# SAME51_PINOUT.net
KiCad netlist of a schematic drawn in Altium Designer
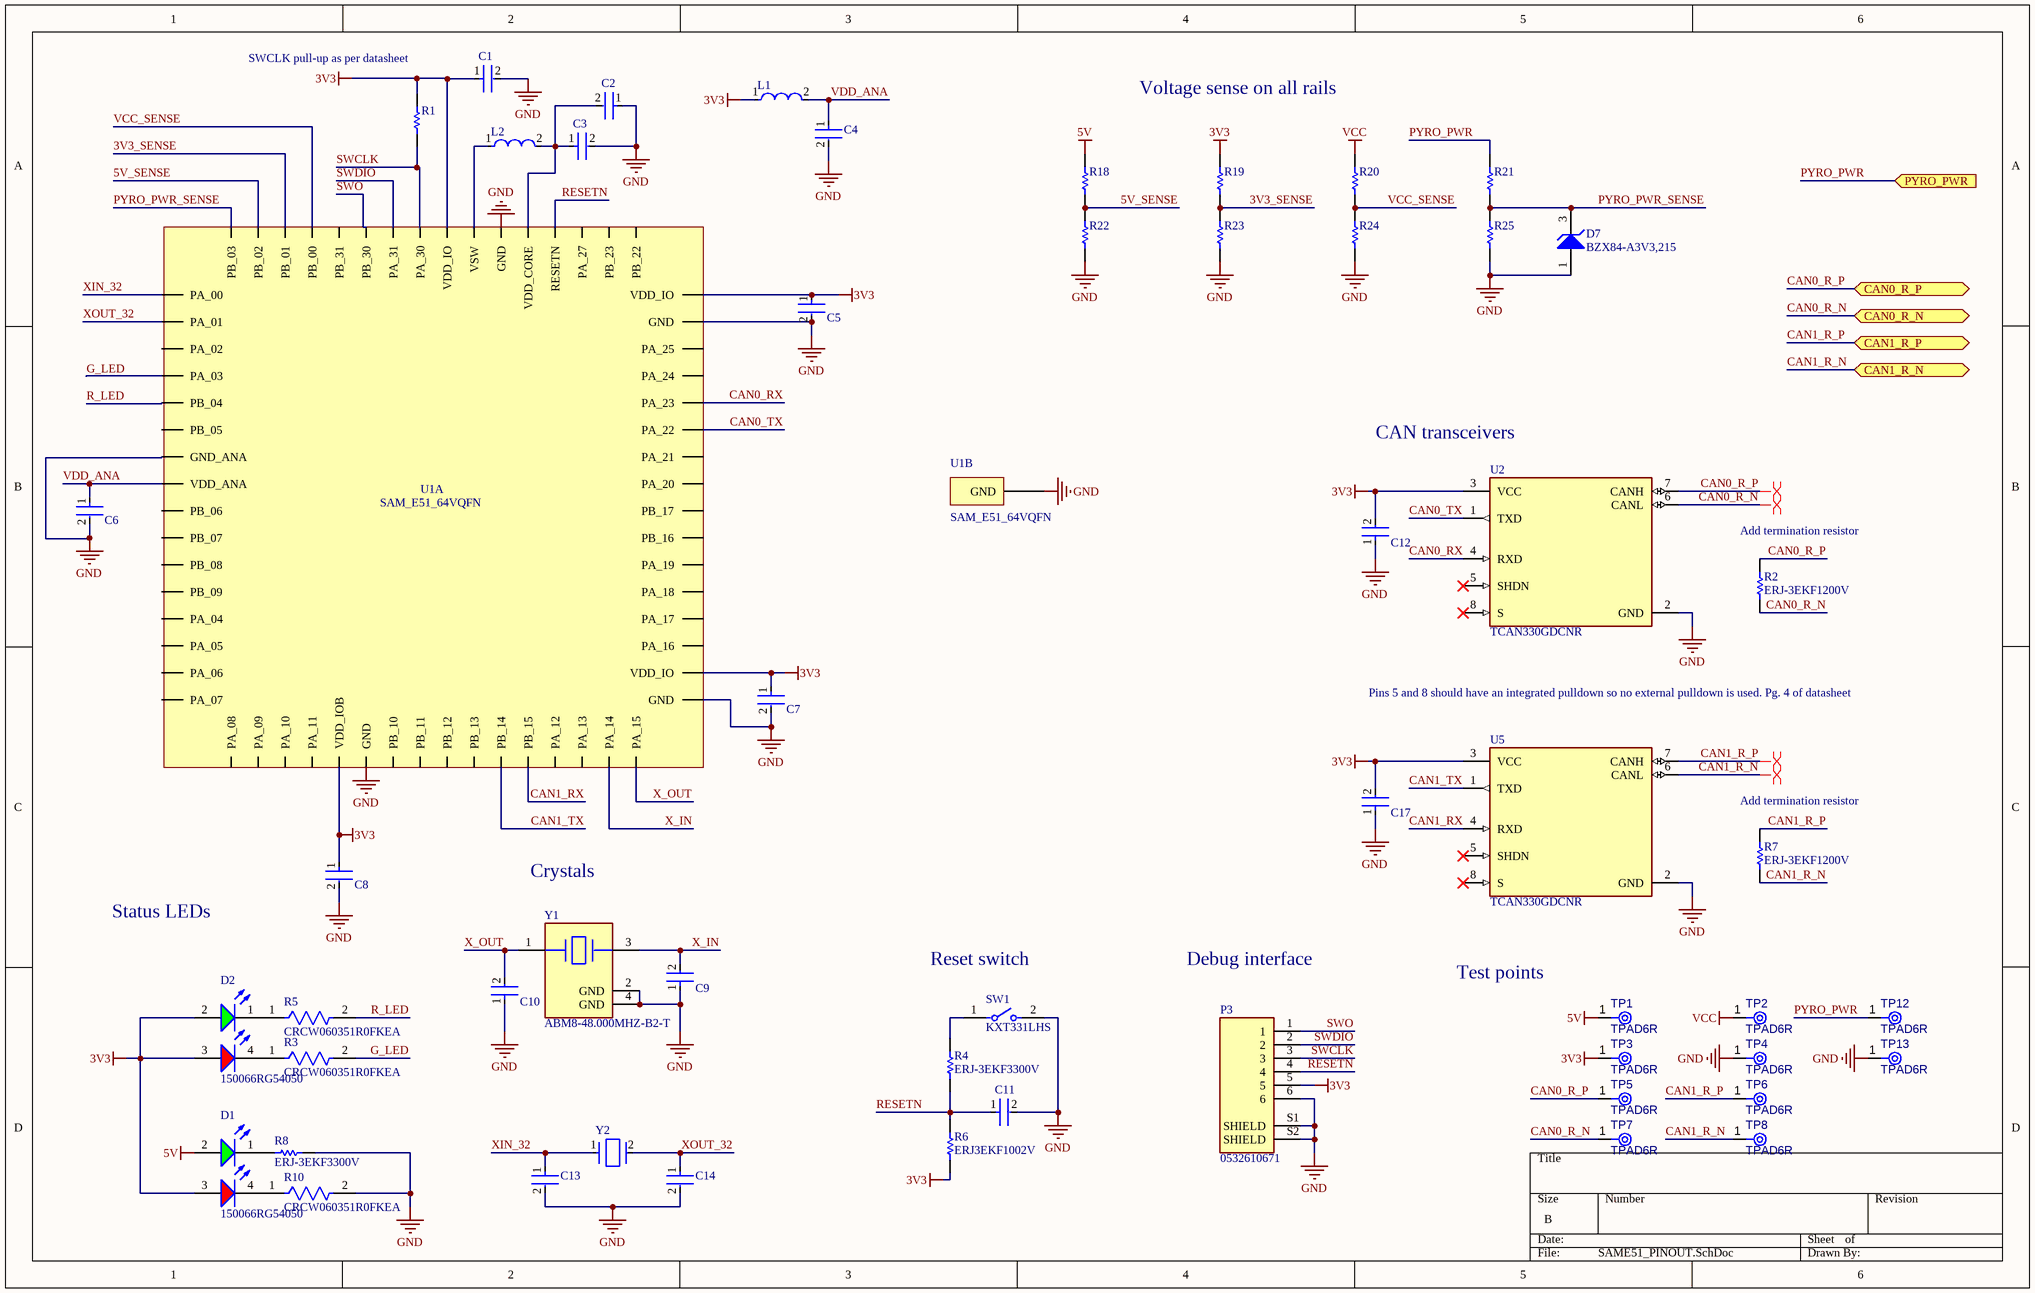
[diagram p0: SAME51_PINOUT.SchDoc]

(export (version "E")
  (design (tool "Eeschema 10.0.6"))
  (components
    (comp (ref "C1")
      (value "C0402C104K8PACTU")
      (footprint "FP-C0402-BB-MFG")
      (description "CAP CER 0.1UF 10V X5R 0402")
      (fields (field (name "MANUFACTURER") "Kemet") (field (name "TOLERANCE") "0.1"))
      (libsource (lib "Altium Content Vault") (part "b4654b650e69147ec39a6b967a45e02"))
    )
    (comp (ref "C2")
      (value "GRM155R60J475ME47D")
      (footprint "FP-GRM155-0_1-IPC_B")
      (description "Chip Multilayer Ceramic Capacitors for General Purpose, 0402, 4.7uF, X5R, 15%, 20%, 6.3V")
      (fields (field (name "VOLTAGE") "6.3V") (field (name "TOLERANCE") "20%"))
      (libsource (lib "Altium Content Vault") (part "11868f565c42a9108669ba33697ecf6"))
    )
    (comp (ref "C3")
      (value "C0402C104K8PACTU")
      (footprint "FP-C0402-BB-MFG")
      (description "CAP CER 0.1UF 10V X5R 0402")
      (fields (field (name "MANUFACTURER") "Kemet") (field (name "TOLERANCE") "0.1"))
      (libsource (lib "Altium Content Vault") (part "b4654b650e69147ec39a6b967a45e02"))
    )
    (comp (ref "C4")
      (value "C0805C106K8PACTU")
      (footprint "FP-C0805C-DG-MFG")
      (description "CAP CER 10UF 10V X5R 0805")
      (fields (field (name "TOLERANCE") "10%") (field (name "MANUFACTURER") "Kemet"))
      (libsource (lib "Altium Content Vault") (part "11868f565c42a9108669ba33697ecf6"))
    )
    (comp (ref "C5")
      (value "C0402C104K8PACTU")
      (footprint "FP-C0402-BB-MFG")
      (description "CAP CER 0.1UF 10V X5R 0402")
      (fields (field (name "MANUFACTURER") "Kemet") (field (name "TOLERANCE") "0.1"))
      (libsource (lib "Altium Content Vault") (part "b4654b650e69147ec39a6b967a45e02"))
    )
    (comp (ref "C6")
      (value "C0402C104K8PACTU")
      (footprint "FP-C0402-BB-MFG")
      (description "CAP CER 0.1UF 10V X5R 0402")
      (fields (field (name "MANUFACTURER") "Kemet") (field (name "TOLERANCE") "0.1"))
      (libsource (lib "Altium Content Vault") (part "b4654b650e69147ec39a6b967a45e02"))
    )
    (comp (ref "C7")
      (value "C0402C104K8PACTU")
      (footprint "FP-C0402-BB-MFG")
      (description "CAP CER 0.1UF 10V X5R 0402")
      (fields (field (name "MANUFACTURER") "Kemet") (field (name "TOLERANCE") "0.1"))
      (libsource (lib "Altium Content Vault") (part "b4654b650e69147ec39a6b967a45e02"))
    )
    (comp (ref "C8")
      (value "C0402C104K8PACTU")
      (footprint "FP-C0402-BB-MFG")
      (description "CAP CER 0.1UF 10V X5R 0402")
      (fields (field (name "MANUFACTURER") "Kemet") (field (name "TOLERANCE") "0.1"))
      (libsource (lib "Altium Content Vault") (part "b4654b650e69147ec39a6b967a45e02"))
    )
    (comp (ref "C9")
      (value "08051A6R8CAT2A")
      (footprint "FP-0805-L_2_01_0_2-W_1_25-MFG")
      (description "General Purpose Ceramic Capacitor, 0805, 6.8pF, 0.25pF, C0G, 30ppm/°C, 100V")
      (fields (field (name "VOLTAGE") "100V") (field (name "TOLERANCE") "5%"))
      (libsource (lib "Altium Content Vault") (part "02cd4be3c70576c341d710602a673aa"))
    )
    (comp (ref "C10")
      (value "08051A6R8CAT2A")
      (footprint "FP-0805-L_2_01_0_2-W_1_25-MFG")
      (description "General Purpose Ceramic Capacitor, 0805, 6.8pF, 0.25pF, C0G, 30ppm/°C, 100V")
      (fields (field (name "VOLTAGE") "100V") (field (name "TOLERANCE") "5%"))
      (libsource (lib "Altium Content Vault") (part "02cd4be3c70576c341d710602a673aa"))
    )
    (comp (ref "C11")
      (value "C0402C104K8PACTU")
      (footprint "FP-C0402-BB-MFG")
      (description "CAP CER 0.1UF 10V X5R 0402")
      (fields (field (name "MANUFACTURER") "Kemet") (field (name "TOLERANCE") "0.1"))
      (libsource (lib "Altium Content Vault") (part "b4654b650e69147ec39a6b967a45e02"))
    )
    (comp (ref "C12")
      (value "C0402C104K8PACTU")
      (footprint "FP-C0402-BB-MFG")
      (description "CAP CER 0.1UF 10V X5R 0402")
      (fields (field (name "MANUFACTURER") "Kemet") (field (name "TOLERANCE") "0.1"))
      (libsource (lib "Altium Content Vault") (part "b4654b650e69147ec39a6b967a45e02"))
    )
    (comp (ref "C13")
      (value "C0805C180J5GACTU")
      (footprint "FP-C0805C-DN-MFG")
      (description "CAP CER 18PF 50V C0G/NP0 0805")
      (fields
        (field (name "OCTOPART") "https://octopart.com/c0805c180j5gactu-kemet-144810")
        (field (name "TOLERANCE") "0.05")
      )
      (libsource (lib "Altium Content Vault") (part "b4654b650e69147ec39a6b967a45e02"))
    )
    (comp (ref "C14")
      (value "C0805C180J5GACTU")
      (footprint "FP-C0805C-DN-MFG")
      (description "CAP CER 18PF 50V C0G/NP0 0805")
      (fields
        (field (name "OCTOPART") "https://octopart.com/c0805c180j5gactu-kemet-144810")
        (field (name "TOLERANCE") "0.05")
      )
      (libsource (lib "Altium Content Vault") (part "b4654b650e69147ec39a6b967a45e02"))
    )
    (comp (ref "C17")
      (value "C0402C104K8PACTU")
      (footprint "FP-C0402-BB-MFG")
      (description "CAP CER 0.1UF 10V X5R 0402")
      (fields (field (name "MANUFACTURER") "Kemet") (field (name "TOLERANCE") "0.1"))
      (libsource (lib "Altium Content Vault") (part "b4654b650e69147ec39a6b967a45e02"))
    )
    (comp (ref "D1")
      (value "150066RG54050")
      (footprint "WL-SBCD_0606")
      (description "Led, Red/Grn, 180Mcd/230Mcd, 624Nm/525Nm Rohs Compliant: Yes")
      (libsource (lib "uORocketry Hardware") (part "WL-SBCD_0606_Red & Green"))
    )
    (comp (ref "D2")
      (value "150066RG54050")
      (footprint "WL-SBCD_0606")
      (description "Led, Red/Grn, 180Mcd/230Mcd, 624Nm/525Nm Rohs Compliant: Yes")
      (libsource (lib "uORocketry Hardware") (part "WL-SBCD_0606_Red & Green"))
    )
    (comp (ref "D7")
      (value "BZX84-A3V3,215")
      (footprint "SOT95P230X110-3N")
      (description "DIODE ZENER 3.3V 250MW SOT23")
      (libsource (lib "uORocketry Hardware") (part "BZX84-A3V3,215"))
    )
    (comp (ref "L1")
      (value "NR6028T100M")
      (footprint "FP-NR6028-MFG")
      (description "SMD Power Inductors 10uH ±20% 1.9A 84.5mΩ")
      (fields (field (name "TOLERANCE") "20%"))
      (libsource (lib "Altium Content Vault") (part "725321dda6339637d4d059423bc1c3c"))
    )
    (comp (ref "L2")
      (value "NR6028T100M")
      (footprint "FP-NR6028-MFG")
      (description "SMD Power Inductors 10uH ±20% 1.9A 84.5mΩ")
      (fields (field (name "TOLERANCE") "20%"))
      (libsource (lib "Altium Content Vault") (part "725321dda6339637d4d059423bc1c3c"))
    )
    (comp (ref "P3")
      (value "0532610671")
      (footprint "0532610671-Footprint-1")
      (description "Conn Shrouded Header (4 Sides) HDR 6 POS 1.25mm Solder RA Side Entry SMD PicoBlade™ T/R")
      (libsource (lib "uORocketry Hardware") (part "0532610671"))
    )
    (comp (ref "R1")
      (value "ERJ3EKF1002V")
      (footprint "RESC1609X55X30LL15T15")
      (description "Chip Resistor, 10 KOhm, +/- 1%, 0.1 W, -55 to 155 degC, 0603 (1608 Metric), RoHS, Tape and Reel")
      (fields (field (name "TOLERANCE") "1%") (field (name "MANUFACTURER") "Panasonic"))
      (libsource (lib "Altium Content Vault") (part "RES-2"))
    )
    (comp (ref "R2")
      (value "ERJ-3EKF1200V")
      (footprint "RESC1609X55X30ML15T15")
      (description "Chip Resistor, 120 Ohm, +/- 1%, 0.1 W, -55 to 155 degC, 0603 (1608 Metric), RoHS, Tape and Reel")
      (fields (field (name "TOLERANCE") "1%") (field (name "MANUFACTURER") "Panasonic"))
      (libsource (lib "Altium Content Vault") (part "RES-2"))
    )
    (comp (ref "R3")
      (value "CRCW060351R0FKEA")
      (footprint "FP-CRCW0603-e3-MFG")
      (description "RES Thick Film, 51Ω, 1%, 0.1W, 100ppm/°C, 0603")
      (fields (field (name "TOLERANCE") "1%"))
      (libsource (lib "Altium Content Vault") (part "1029c3af85768c4190bb7ad29bc67b5"))
    )
    (comp (ref "R4")
      (value "ERJ-3EKF3300V")
      (footprint "RESC1608X55X30LL15T15")
      (description "Chip Resistor, 330 Ohm, +/- 1%, 0.1 W, -55 to 155 degC, 0603 (1608 Metric), RoHS, Tape and Reel")
      (libsource (lib "Altium Content Vault") (part "RES-2"))
    )
    (comp (ref "R5")
      (value "CRCW060351R0FKEA")
      (footprint "FP-CRCW0603-e3-MFG")
      (description "RES Thick Film, 51Ω, 1%, 0.1W, 100ppm/°C, 0603")
      (fields (field (name "TOLERANCE") "1%"))
      (libsource (lib "Altium Content Vault") (part "1029c3af85768c4190bb7ad29bc67b5"))
    )
    (comp (ref "R6")
      (value "ERJ3EKF1002V")
      (footprint "RESC1609X55X30LL15T15")
      (description "Chip Resistor, 10 KOhm, +/- 1%, 0.1 W, -55 to 155 degC, 0603 (1608 Metric), RoHS, Tape and Reel")
      (fields (field (name "TOLERANCE") "1%") (field (name "MANUFACTURER") "Panasonic"))
      (libsource (lib "Altium Content Vault") (part "RES-2"))
    )
    (comp (ref "R7")
      (value "ERJ-3EKF1200V")
      (footprint "RESC1609X55X30ML15T15")
      (description "Chip Resistor, 120 Ohm, +/- 1%, 0.1 W, -55 to 155 degC, 0603 (1608 Metric), RoHS, Tape and Reel")
      (fields (field (name "TOLERANCE") "1%") (field (name "MANUFACTURER") "Panasonic"))
      (libsource (lib "Altium Content Vault") (part "RES-2"))
    )
    (comp (ref "R8")
      (value "ERJ-3EKF3300V")
      (footprint "RESC1608X55X30LL15T15")
      (description "Chip Resistor, 330 Ohm, +/- 1%, 0.1 W, -55 to 155 degC, 0603 (1608 Metric), RoHS, Tape and Reel")
      (libsource (lib "Altium Content Vault") (part "RES-2"))
    )
    (comp (ref "R10")
      (value "CRCW060351R0FKEA")
      (footprint "FP-CRCW0603-e3-MFG")
      (description "RES Thick Film, 51Ω, 1%, 0.1W, 100ppm/°C, 0603")
      (fields (field (name "TOLERANCE") "1%"))
      (libsource (lib "Altium Content Vault") (part "1029c3af85768c4190bb7ad29bc67b5"))
    )
    (comp (ref "R18")
      (value "ERJ3EKF1002V")
      (footprint "RESC1609X55X30LL15T15")
      (description "Chip Resistor, 10 KOhm, +/- 1%, 0.1 W, -55 to 155 degC, 0603 (1608 Metric), RoHS, Tape and Reel")
      (fields (field (name "TOLERANCE") "1%") (field (name "MANUFACTURER") "Panasonic"))
      (libsource (lib "Altium Content Vault") (part "RES-2"))
    )
    (comp (ref "R19")
      (value "ERJ3EKF1002V")
      (footprint "RESC1609X55X30LL15T15")
      (description "Chip Resistor, 10 KOhm, +/- 1%, 0.1 W, -55 to 155 degC, 0603 (1608 Metric), RoHS, Tape and Reel")
      (fields (field (name "TOLERANCE") "1%") (field (name "MANUFACTURER") "Panasonic"))
      (libsource (lib "Altium Content Vault") (part "RES-2"))
    )
    (comp (ref "R20")
      (value "ERJ3EKF1002V")
      (footprint "RESC1609X55X30LL15T15")
      (description "Chip Resistor, 10 KOhm, +/- 1%, 0.1 W, -55 to 155 degC, 0603 (1608 Metric), RoHS, Tape and Reel")
      (fields (field (name "TOLERANCE") "1%") (field (name "MANUFACTURER") "Panasonic"))
      (libsource (lib "Altium Content Vault") (part "RES-2"))
    )
    (comp (ref "R21")
      (value "ERJ3EKF1002V")
      (footprint "RESC1609X55X30LL15T15")
      (description "Chip Resistor, 10 KOhm, +/- 1%, 0.1 W, -55 to 155 degC, 0603 (1608 Metric), RoHS, Tape and Reel")
      (fields (field (name "TOLERANCE") "1%") (field (name "MANUFACTURER") "Panasonic"))
      (libsource (lib "Altium Content Vault") (part "RES-2"))
    )
    (comp (ref "R22")
      (value "ERJ3EKF1002V")
      (footprint "RESC1609X55X30LL15T15")
      (description "Chip Resistor, 10 KOhm, +/- 1%, 0.1 W, -55 to 155 degC, 0603 (1608 Metric), RoHS, Tape and Reel")
      (fields (field (name "TOLERANCE") "1%") (field (name "MANUFACTURER") "Panasonic"))
      (libsource (lib "Altium Content Vault") (part "RES-2"))
    )
    (comp (ref "R23")
      (value "ERJ3EKF1002V")
      (footprint "RESC1609X55X30LL15T15")
      (description "Chip Resistor, 10 KOhm, +/- 1%, 0.1 W, -55 to 155 degC, 0603 (1608 Metric), RoHS, Tape and Reel")
      (fields (field (name "TOLERANCE") "1%") (field (name "MANUFACTURER") "Panasonic"))
      (libsource (lib "Altium Content Vault") (part "RES-2"))
    )
    (comp (ref "R24")
      (value "CRCW06032K70JNEA")
      (footprint "RESC1609X50X30ML10T20")
      (fields (field (name "MANUFACTURER") "Vishay Dale"))
      (libsource (lib "Altium Content Vault") (part "RES"))
    )
    (comp (ref "R25")
      (value "CRCW06032K70JNEA")
      (footprint "RESC1609X50X30ML10T20")
      (fields (field (name "MANUFACTURER") "Vishay Dale"))
      (libsource (lib "Altium Content Vault") (part "RES"))
    )
    (comp (ref "SW1")
      (value "KXT331LHS")
      (footprint "FP-KXT331LHS-MFG")
      (description "SWITCH TACTILE SPST-NO 0.02A 15V")
      (libsource (lib "Altium Content Vault") (part "bb27bde45df87f1f469753f287ef5ae"))
    )
    (comp (ref "TP1")
      (value "TPAD6R")
      (footprint "TP06R")
      (description "0.6mm round")
      (libsource (lib "uORocketry Hardware") (part "CMP-001-0001-4"))
    )
    (comp (ref "TP2")
      (value "TPAD6R")
      (footprint "TP06R")
      (description "0.6mm round")
      (libsource (lib "uORocketry Hardware") (part "CMP-001-0001-4"))
    )
    (comp (ref "TP3")
      (value "TPAD6R")
      (footprint "TP06R")
      (description "0.6mm round")
      (libsource (lib "uORocketry Hardware") (part "CMP-001-0001-4"))
    )
    (comp (ref "TP4")
      (value "TPAD6R")
      (footprint "TP06R")
      (description "0.6mm round")
      (libsource (lib "uORocketry Hardware") (part "CMP-001-0001-4"))
    )
    (comp (ref "TP5")
      (value "TPAD6R")
      (footprint "TP06R")
      (description "0.6mm round")
      (libsource (lib "uORocketry Hardware") (part "CMP-001-0001-4"))
    )
    (comp (ref "TP6")
      (value "TPAD6R")
      (footprint "TP06R")
      (description "0.6mm round")
      (libsource (lib "uORocketry Hardware") (part "CMP-001-0001-4"))
    )
    (comp (ref "TP7")
      (value "TPAD6R")
      (footprint "TP06R")
      (description "0.6mm round")
      (libsource (lib "uORocketry Hardware") (part "CMP-001-0001-4"))
    )
    (comp (ref "TP8")
      (value "TPAD6R")
      (footprint "TP06R")
      (description "0.6mm round")
      (libsource (lib "uORocketry Hardware") (part "CMP-001-0001-4"))
    )
    (comp (ref "TP12")
      (value "TPAD6R")
      (footprint "TP06R")
      (description "0.6mm round")
      (libsource (lib "uORocketry Hardware") (part "CMP-001-0001-4"))
    )
    (comp (ref "TP13")
      (value "TPAD6R")
      (footprint "TP06R")
      (description "0.6mm round")
      (libsource (lib "uORocketry Hardware") (part "CMP-001-0001-4"))
    )
    (comp (ref "U1")
      (value "SAM_E51_64VQFN")
      (footprint "SAM_E51_64VQFN-Footprint-1")
      (description "Rudimentary symbol and footprint for the SAM E51 microcontroller")
      (libsource (lib "uORocketry Hardware") (part "SAM_E51_64VQFN-Symbol-1"))
    )
    (comp (ref "U2")
      (value "TCAN330GDCNR")
      (footprint "FP-DCN0008A-MFG")
      (description "IC TRANSCEIVER 1/1 SOT23-8")
      (libsource (lib "Altium Content Vault") (part "22681b49c22ad38c6a4e12e04c36c7a"))
    )
    (comp (ref "U5")
      (value "TCAN330GDCNR")
      (footprint "FP-DCN0008A-MFG")
      (description "IC TRANSCEIVER 1/1 SOT23-8")
      (libsource (lib "Altium Content Vault") (part "22681b49c22ad38c6a4e12e04c36c7a"))
    )
    (comp (ref "Y1")
      (value "ABM8-48.000MHZ-B2-T")
      (footprint "FP-ABM8-MFG")
      (description "Crystal 48MHz ±20ppm 18pF SMD-4 3.2mm x 2.5mm")
      (fields (field (name "TOLERANCE") "20ppm"))
      (libsource (lib "Altium Content Vault") (part "dfdb7f9a12507849fb681da9a70121c"))
    )
    (comp (ref "Y2")
      (value "ECS-.327-12.5-1210-TR")
      (footprint "FP-ECX-1210-MFG")
      (description "CRYSTAL 32.7680KHZ 12.5PF SMD")
      (fields
        (field (name "OCTOPART") "https://octopart.com/ecs-.327-12.5-1210-tr-ecs+international-81221340")
        (field (name "TOLERANCE") "20ppm")
      )
      (libsource (lib "Altium Content Vault") (part "99724985039315a44fd0d1401b84e49"))
    )
  )
  (nets
    (net (code "1") (name "/3V3_SENSE") (class "Default")
      (node (ref "R19") (pin "1") (pinfunction "1_1") (pintype "passive"))
      (node (ref "R23") (pin "2") (pinfunction "2_2") (pintype "passive"))
      (node (ref "U1") (pin "62") (pinfunction "PB_01_62") (pintype "passive"))
    )
    (net (code "2") (name "/5V_SENSE") (class "Default")
      (node (ref "R18") (pin "1") (pinfunction "1_1") (pintype "passive"))
      (node (ref "R22") (pin "2") (pinfunction "2_2") (pintype "passive"))
      (node (ref "U1") (pin "63") (pinfunction "PB_02_63") (pintype "passive"))
    )
    (net (code "3") (name "/CAN0_RX") (class "Default")
      (node (ref "U1") (pin "44") (pinfunction "PA_23_44") (pintype "passive"))
      (node (ref "U2") (pin "4") (pinfunction "RXD_4") (pintype "input"))
    )
    (net (code "4") (name "/CAN0_R_N") (class "Default")
      (node (ref "R2") (pin "1") (pinfunction "1_1") (pintype "passive"))
      (node (ref "TP7") (pin "1") (pinfunction "TP_1") (pintype "passive"))
      (node (ref "U2") (pin "6") (pinfunction "CANL_6") (pintype "bidirectional"))
    )
    (net (code "5") (name "/CAN0_R_P") (class "Default")
      (node (ref "R2") (pin "2") (pinfunction "2_2") (pintype "passive"))
      (node (ref "TP5") (pin "1") (pinfunction "TP_1") (pintype "passive"))
      (node (ref "U2") (pin "7") (pinfunction "CANH_7") (pintype "bidirectional"))
    )
    (net (code "6") (name "/CAN0_TX") (class "Default")
      (node (ref "U1") (pin "43") (pinfunction "PA_22_43") (pintype "passive"))
      (node (ref "U2") (pin "1") (pinfunction "TXD_1") (pintype "output"))
    )
    (net (code "7") (name "/CAN1_RX") (class "Default")
      (node (ref "U1") (pin "28") (pinfunction "PB_15_28") (pintype "passive"))
      (node (ref "U5") (pin "4") (pinfunction "RXD_4") (pintype "input"))
    )
    (net (code "8") (name "/CAN1_R_N") (class "Default")
      (node (ref "R7") (pin "1") (pinfunction "1_1") (pintype "passive"))
      (node (ref "TP8") (pin "1") (pinfunction "TP_1") (pintype "passive"))
      (node (ref "U5") (pin "6") (pinfunction "CANL_6") (pintype "bidirectional"))
    )
    (net (code "9") (name "/CAN1_R_P") (class "Default")
      (node (ref "R7") (pin "2") (pinfunction "2_2") (pintype "passive"))
      (node (ref "TP6") (pin "1") (pinfunction "TP_1") (pintype "passive"))
      (node (ref "U5") (pin "7") (pinfunction "CANH_7") (pintype "bidirectional"))
    )
    (net (code "10") (name "/CAN1_TX") (class "Default")
      (node (ref "U1") (pin "27") (pinfunction "PB_14_27") (pintype "passive"))
      (node (ref "U5") (pin "1") (pinfunction "TXD_1") (pintype "output"))
    )
    (net (code "11") (name "/G_LED") (class "Default")
      (node (ref "R3") (pin "2") (pinfunction "2_2") (pintype "passive"))
      (node (ref "U1") (pin "4") (pinfunction "PA_03_4") (pintype "passive"))
    )
    (net (code "12") (name "/PYRO_PWR") (class "Default")
      (node (ref "R21") (pin "2") (pinfunction "2_2") (pintype "passive"))
      (node (ref "TP12") (pin "1") (pinfunction "TP_1") (pintype "passive"))
    )
    (net (code "13") (name "/PYRO_PWR_SENSE") (class "Default")
      (node (ref "D7") (pin "3") (pinfunction "K_3") (pintype "passive"))
      (node (ref "R21") (pin "1") (pinfunction "1_1") (pintype "passive"))
      (node (ref "R25") (pin "2") (pinfunction "2_2") (pintype "passive"))
      (node (ref "U1") (pin "64") (pinfunction "PB_03_64") (pintype "passive"))
    )
    (net (code "14") (name "/RESETN") (class "Default")
      (node (ref "C11") (pin "1") (pinfunction "1_1") (pintype "passive"))
      (node (ref "P3") (pin "4") (pinfunction "4_4") (pintype "passive"))
      (node (ref "R4") (pin "1") (pinfunction "1_1") (pintype "passive"))
      (node (ref "R6") (pin "2") (pinfunction "2_2") (pintype "passive"))
      (node (ref "U1") (pin "52") (pinfunction "RESETN_52") (pintype "passive"))
    )
    (net (code "15") (name "/R_LED") (class "Default")
      (node (ref "R5") (pin "2") (pinfunction "2_2") (pintype "passive"))
      (node (ref "U1") (pin "5") (pinfunction "PB_04_5") (pintype "passive"))
    )
    (net (code "16") (name "/SWCLK") (class "Default")
      (node (ref "P3") (pin "3") (pinfunction "3_3") (pintype "passive"))
      (node (ref "R1") (pin "1") (pinfunction "1_1") (pintype "passive"))
      (node (ref "U1") (pin "57") (pinfunction "PA_30_57") (pintype "passive"))
    )
    (net (code "17") (name "/SWDIO") (class "Default")
      (node (ref "P3") (pin "2") (pinfunction "2_2") (pintype "passive"))
      (node (ref "U1") (pin "58") (pinfunction "PA_31_58") (pintype "passive"))
    )
    (net (code "18") (name "/SWO") (class "Default")
      (node (ref "P3") (pin "1") (pinfunction "1_1") (pintype "passive"))
      (node (ref "U1") (pin "59") (pinfunction "PB_30_59") (pintype "passive"))
    )
    (net (code "19") (name "/VCC_SENSE") (class "Default")
      (node (ref "R20") (pin "1") (pinfunction "1_1") (pintype "passive"))
      (node (ref "R24") (pin "2") (pinfunction "2_2") (pintype "passive"))
      (node (ref "U1") (pin "61") (pinfunction "PB_00_61") (pintype "passive"))
    )
    (net (code "20") (name "/VDD_ANA") (class "Default")
      (node (ref "C4") (pin "1") (pinfunction "1_1") (pintype "passive"))
      (node (ref "C6") (pin "1") (pinfunction "1_1") (pintype "passive"))
      (node (ref "L1") (pin "2") (pinfunction "2_2") (pintype "passive"))
      (node (ref "U1") (pin "8") (pinfunction "VDD_ANA_8") (pintype "passive"))
    )
    (net (code "21") (name "/XIN_32") (class "Default")
      (node (ref "C13") (pin "1") (pinfunction "1_1") (pintype "passive"))
      (node (ref "U1") (pin "1") (pinfunction "PA_00_1") (pintype "passive"))
      (node (ref "Y2") (pin "1") (pinfunction "In/Out_1") (pintype "passive"))
    )
    (net (code "22") (name "/XOUT_32") (class "Default")
      (node (ref "C14") (pin "1") (pinfunction "1_1") (pintype "passive"))
      (node (ref "U1") (pin "2") (pinfunction "PA_01_2") (pintype "passive"))
      (node (ref "Y2") (pin "2") (pinfunction "Out/In_2") (pintype "passive"))
    )
    (net (code "23") (name "/X_IN") (class "Default")
      (node (ref "C9") (pin "2") (pinfunction "2_2") (pintype "passive"))
      (node (ref "U1") (pin "31") (pinfunction "PA_14_31") (pintype "passive"))
      (node (ref "Y1") (pin "3") (pinfunction "3_3") (pintype "passive"))
    )
    (net (code "24") (name "/X_OUT") (class "Default")
      (node (ref "C10") (pin "2") (pinfunction "2_2") (pintype "passive"))
      (node (ref "U1") (pin "32") (pinfunction "PA_15_32") (pintype "passive"))
      (node (ref "Y1") (pin "1") (pinfunction "1_1") (pintype "passive"))
    )
    (net (code "25") (name "3V3") (class "Default")
      (node (ref "C1") (pin "1") (pinfunction "1_1") (pintype "passive"))
      (node (ref "C12") (pin "2") (pinfunction "2_2") (pintype "passive"))
      (node (ref "C17") (pin "2") (pinfunction "2_2") (pintype "passive"))
      (node (ref "C5") (pin "1") (pinfunction "1_1") (pintype "passive"))
      (node (ref "C7") (pin "1") (pinfunction "1_1") (pintype "passive"))
      (node (ref "C8") (pin "1") (pinfunction "1_1") (pintype "passive"))
      (node (ref "D1") (pin "3") (pinfunction "A_3") (pintype "passive"))
      (node (ref "D2") (pin "2") (pinfunction "A_2") (pintype "passive"))
      (node (ref "D2") (pin "3") (pinfunction "A_3") (pintype "passive"))
      (node (ref "L1") (pin "1") (pinfunction "1_1") (pintype "passive"))
      (node (ref "P3") (pin "5") (pinfunction "5_5") (pintype "passive"))
      (node (ref "R1") (pin "2") (pinfunction "2_2") (pintype "passive"))
      (node (ref "R19") (pin "2") (pinfunction "2_2") (pintype "passive"))
      (node (ref "R6") (pin "1") (pinfunction "1_1") (pintype "passive"))
      (node (ref "TP3") (pin "1") (pinfunction "TP_1") (pintype "passive"))
      (node (ref "U1") (pin "21") (pinfunction "VDD_IOB_21") (pintype "passive"))
      (node (ref "U1") (pin "34") (pinfunction "VDD_IO_34") (pintype "passive"))
      (node (ref "U1") (pin "48") (pinfunction "VDD_IO_48") (pintype "passive"))
      (node (ref "U1") (pin "56") (pinfunction "VDD_IO_56") (pintype "passive"))
      (node (ref "U2") (pin "3") (pinfunction "VCC_3") (pintype "power_in"))
      (node (ref "U5") (pin "3") (pinfunction "VCC_3") (pintype "power_in"))
    )
    (net (code "26") (name "5V") (class "Default")
      (node (ref "D1") (pin "2") (pinfunction "A_2") (pintype "passive"))
      (node (ref "R18") (pin "2") (pinfunction "2_2") (pintype "passive"))
      (node (ref "TP1") (pin "1") (pinfunction "TP_1") (pintype "passive"))
    )
    (net (code "27") (name "GND") (class "Default")
      (node (ref "C1") (pin "2") (pinfunction "2_2") (pintype "passive"))
      (node (ref "C10") (pin "1") (pinfunction "1_1") (pintype "passive"))
      (node (ref "C11") (pin "2") (pinfunction "2_2") (pintype "passive"))
      (node (ref "C12") (pin "1") (pinfunction "1_1") (pintype "passive"))
      (node (ref "C13") (pin "2") (pinfunction "2_2") (pintype "passive"))
      (node (ref "C14") (pin "2") (pinfunction "2_2") (pintype "passive"))
      (node (ref "C17") (pin "1") (pinfunction "1_1") (pintype "passive"))
      (node (ref "C2") (pin "1") (pinfunction "1_1") (pintype "passive"))
      (node (ref "C3") (pin "2") (pinfunction "2_2") (pintype "passive"))
      (node (ref "C4") (pin "2") (pinfunction "2_2") (pintype "passive"))
      (node (ref "C5") (pin "2") (pinfunction "2_2") (pintype "passive"))
      (node (ref "C6") (pin "2") (pinfunction "2_2") (pintype "passive"))
      (node (ref "C7") (pin "2") (pinfunction "2_2") (pintype "passive"))
      (node (ref "C8") (pin "2") (pinfunction "2_2") (pintype "passive"))
      (node (ref "C9") (pin "1") (pinfunction "1_1") (pintype "passive"))
      (node (ref "D7") (pin "1") (pinfunction "A_1") (pintype "passive"))
      (node (ref "P3") (pin "6") (pinfunction "6_6") (pintype "passive"))
      (node (ref "P3") (pin "S1") (pinfunction "SHIELD_S1") (pintype "passive"))
      (node (ref "P3") (pin "S2") (pinfunction "SHIELD_S2") (pintype "passive"))
      (node (ref "R10") (pin "2") (pinfunction "2_2") (pintype "passive"))
      (node (ref "R22") (pin "1") (pinfunction "1_1") (pintype "passive"))
      (node (ref "R23") (pin "1") (pinfunction "1_1") (pintype "passive"))
      (node (ref "R24") (pin "1") (pinfunction "1_1") (pintype "passive"))
      (node (ref "R25") (pin "1") (pinfunction "1_1") (pintype "passive"))
      (node (ref "R8") (pin "2") (pinfunction "2_2") (pintype "passive"))
      (node (ref "SW1") (pin "2") (pinfunction "2_2") (pintype "passive"))
      (node (ref "TP13") (pin "1") (pinfunction "TP_1") (pintype "passive"))
      (node (ref "TP4") (pin "1") (pinfunction "TP_1") (pintype "passive"))
      (node (ref "U1") (pin "22") (pinfunction "GND_22") (pintype "passive"))
      (node (ref "U1") (pin "33") (pinfunction "GND_33") (pintype "passive"))
      (node (ref "U1") (pin "47") (pinfunction "GND_47") (pintype "passive"))
      (node (ref "U1") (pin "54") (pinfunction "GND_54") (pintype "passive"))
      (node (ref "U1") (pin "65") (pinfunction "GND_65") (pintype "passive"))
      (node (ref "U1") (pin "7") (pinfunction "GND_ANA_7") (pintype "passive"))
      (node (ref "U2") (pin "2") (pinfunction "GND_2") (pintype "power_in"))
      (node (ref "U5") (pin "2") (pinfunction "GND_2") (pintype "power_in"))
      (node (ref "Y1") (pin "2") (pinfunction "GND_2") (pintype "power_in"))
      (node (ref "Y1") (pin "4") (pinfunction "GND_4") (pintype "power_in"))
    )
    (net (code "28") (name "Net-(D1-K-Pad1)") (class "Default")
      (node (ref "D1") (pin "1") (pinfunction "K_1") (pintype "passive"))
      (node (ref "R8") (pin "1") (pinfunction "1_1") (pintype "passive"))
    )
    (net (code "29") (name "Net-(D1-K-Pad4)") (class "Default")
      (node (ref "D1") (pin "4") (pinfunction "K_4") (pintype "passive"))
      (node (ref "R10") (pin "1") (pinfunction "1_1") (pintype "passive"))
    )
    (net (code "30") (name "Net-(D2-K-Pad1)") (class "Default")
      (node (ref "D2") (pin "1") (pinfunction "K_1") (pintype "passive"))
      (node (ref "R5") (pin "1") (pinfunction "1_1") (pintype "passive"))
    )
    (net (code "31") (name "Net-(D2-K-Pad4)") (class "Default")
      (node (ref "D2") (pin "4") (pinfunction "K_4") (pintype "passive"))
      (node (ref "R3") (pin "1") (pinfunction "1_1") (pintype "passive"))
    )
    (net (code "32") (name "Net-(R4-Pad2)") (class "Default")
      (node (ref "R4") (pin "2") (pinfunction "2_2") (pintype "passive"))
      (node (ref "SW1") (pin "1") (pinfunction "1_1") (pintype "passive"))
    )
    (net (code "33") (name "Net-(U1A-VDD_CORE)") (class "Default")
      (node (ref "C2") (pin "2") (pinfunction "2_2") (pintype "passive"))
      (node (ref "C3") (pin "1") (pinfunction "1_1") (pintype "passive"))
      (node (ref "L2") (pin "2") (pinfunction "2_2") (pintype "passive"))
      (node (ref "U1") (pin "53") (pinfunction "VDD_CORE_53") (pintype "passive"))
    )
    (net (code "34") (name "Net-(U1A-VSW)") (class "Default")
      (node (ref "L2") (pin "1") (pinfunction "1_1") (pintype "passive"))
      (node (ref "U1") (pin "55") (pinfunction "VSW_55") (pintype "passive"))
    )
    (net (code "35") (name "VCC") (class "Default")
      (node (ref "R20") (pin "2") (pinfunction "2_2") (pintype "passive"))
      (node (ref "TP2") (pin "1") (pinfunction "TP_1") (pintype "passive"))
    )
    (net (code "36") (name "unconnected-(U1A-PA_02-Pad3)") (class "Default")
      (node (ref "U1") (pin "3") (pinfunction "PA_02_3") (pintype "passive"))
    )
    (net (code "37") (name "unconnected-(U1A-PA_04-Pad13)") (class "Default")
      (node (ref "U1") (pin "13") (pinfunction "PA_04_13") (pintype "passive"))
    )
    (net (code "38") (name "unconnected-(U1A-PA_05-Pad14)") (class "Default")
      (node (ref "U1") (pin "14") (pinfunction "PA_05_14") (pintype "passive"))
    )
    (net (code "39") (name "unconnected-(U1A-PA_06-Pad15)") (class "Default")
      (node (ref "U1") (pin "15") (pinfunction "PA_06_15") (pintype "passive"))
    )
    (net (code "40") (name "unconnected-(U1A-PA_07-Pad16)") (class "Default")
      (node (ref "U1") (pin "16") (pinfunction "PA_07_16") (pintype "passive"))
    )
    (net (code "41") (name "unconnected-(U1A-PA_08-Pad17)") (class "Default")
      (node (ref "U1") (pin "17") (pinfunction "PA_08_17") (pintype "passive"))
    )
    (net (code "42") (name "unconnected-(U1A-PA_09-Pad18)") (class "Default")
      (node (ref "U1") (pin "18") (pinfunction "PA_09_18") (pintype "passive"))
    )
    (net (code "43") (name "unconnected-(U1A-PA_10-Pad19)") (class "Default")
      (node (ref "U1") (pin "19") (pinfunction "PA_10_19") (pintype "passive"))
    )
    (net (code "44") (name "unconnected-(U1A-PA_11-Pad20)") (class "Default")
      (node (ref "U1") (pin "20") (pinfunction "PA_11_20") (pintype "passive"))
    )
    (net (code "45") (name "unconnected-(U1A-PA_12-Pad29)") (class "Default")
      (node (ref "U1") (pin "29") (pinfunction "PA_12_29") (pintype "passive"))
    )
    (net (code "46") (name "unconnected-(U1A-PA_13-Pad30)") (class "Default")
      (node (ref "U1") (pin "30") (pinfunction "PA_13_30") (pintype "passive"))
    )
    (net (code "47") (name "unconnected-(U1A-PA_16-Pad35)") (class "Default")
      (node (ref "U1") (pin "35") (pinfunction "PA_16_35") (pintype "passive"))
    )
    (net (code "48") (name "unconnected-(U1A-PA_17-Pad36)") (class "Default")
      (node (ref "U1") (pin "36") (pinfunction "PA_17_36") (pintype "passive"))
    )
    (net (code "49") (name "unconnected-(U1A-PA_18-Pad37)") (class "Default")
      (node (ref "U1") (pin "37") (pinfunction "PA_18_37") (pintype "passive"))
    )
    (net (code "50") (name "unconnected-(U1A-PA_19-Pad38)") (class "Default")
      (node (ref "U1") (pin "38") (pinfunction "PA_19_38") (pintype "passive"))
    )
    (net (code "51") (name "unconnected-(U1A-PA_20-Pad41)") (class "Default")
      (node (ref "U1") (pin "41") (pinfunction "PA_20_41") (pintype "passive"))
    )
    (net (code "52") (name "unconnected-(U1A-PA_21-Pad42)") (class "Default")
      (node (ref "U1") (pin "42") (pinfunction "PA_21_42") (pintype "passive"))
    )
    (net (code "53") (name "unconnected-(U1A-PA_24-Pad45)") (class "Default")
      (node (ref "U1") (pin "45") (pinfunction "PA_24_45") (pintype "passive"))
    )
    (net (code "54") (name "unconnected-(U1A-PA_25-Pad46)") (class "Default")
      (node (ref "U1") (pin "46") (pinfunction "PA_25_46") (pintype "passive"))
    )
    (net (code "55") (name "unconnected-(U1A-PA_27-Pad51)") (class "Default")
      (node (ref "U1") (pin "51") (pinfunction "PA_27_51") (pintype "passive"))
    )
    (net (code "56") (name "unconnected-(U1A-PB_05-Pad6)") (class "Default")
      (node (ref "U1") (pin "6") (pinfunction "PB_05_6") (pintype "passive"))
    )
    (net (code "57") (name "unconnected-(U1A-PB_06-Pad9)") (class "Default")
      (node (ref "U1") (pin "9") (pinfunction "PB_06_9") (pintype "passive"))
    )
    (net (code "58") (name "unconnected-(U1A-PB_07-Pad10)") (class "Default")
      (node (ref "U1") (pin "10") (pinfunction "PB_07_10") (pintype "passive"))
    )
    (net (code "59") (name "unconnected-(U1A-PB_08-Pad11)") (class "Default")
      (node (ref "U1") (pin "11") (pinfunction "PB_08_11") (pintype "passive"))
    )
    (net (code "60") (name "unconnected-(U1A-PB_09-Pad12)") (class "Default")
      (node (ref "U1") (pin "12") (pinfunction "PB_09_12") (pintype "passive"))
    )
    (net (code "61") (name "unconnected-(U1A-PB_10-Pad23)") (class "Default")
      (node (ref "U1") (pin "23") (pinfunction "PB_10_23") (pintype "passive"))
    )
    (net (code "62") (name "unconnected-(U1A-PB_11-Pad24)") (class "Default")
      (node (ref "U1") (pin "24") (pinfunction "PB_11_24") (pintype "passive"))
    )
    (net (code "63") (name "unconnected-(U1A-PB_12-Pad25)") (class "Default")
      (node (ref "U1") (pin "25") (pinfunction "PB_12_25") (pintype "passive"))
    )
    (net (code "64") (name "unconnected-(U1A-PB_13-Pad26)") (class "Default")
      (node (ref "U1") (pin "26") (pinfunction "PB_13_26") (pintype "passive"))
    )
    (net (code "65") (name "unconnected-(U1A-PB_16-Pad39)") (class "Default")
      (node (ref "U1") (pin "39") (pinfunction "PB_16_39") (pintype "passive"))
    )
    (net (code "66") (name "unconnected-(U1A-PB_17-Pad40)") (class "Default")
      (node (ref "U1") (pin "40") (pinfunction "PB_17_40") (pintype "passive"))
    )
    (net (code "67") (name "unconnected-(U1A-PB_22-Pad49)") (class "Default")
      (node (ref "U1") (pin "49") (pinfunction "PB_22_49") (pintype "passive"))
    )
    (net (code "68") (name "unconnected-(U1A-PB_23-Pad50)") (class "Default")
      (node (ref "U1") (pin "50") (pinfunction "PB_23_50") (pintype "passive"))
    )
    (net (code "69") (name "unconnected-(U1A-PB_31-Pad60)") (class "Default")
      (node (ref "U1") (pin "60") (pinfunction "PB_31_60") (pintype "passive"))
    )
    (net (code "70") (name "unconnected-(U2-S-Pad8)") (class "Default")
      (node (ref "U2") (pin "8") (pinfunction "S_8") (pintype "input+no_connect"))
    )
    (net (code "71") (name "unconnected-(U2-SHDN-Pad5)") (class "Default")
      (node (ref "U2") (pin "5") (pinfunction "SHDN_5") (pintype "input+no_connect"))
    )
    (net (code "72") (name "unconnected-(U5-S-Pad8)") (class "Default")
      (node (ref "U5") (pin "8") (pinfunction "S_8") (pintype "input+no_connect"))
    )
    (net (code "73") (name "unconnected-(U5-SHDN-Pad5)") (class "Default")
      (node (ref "U5") (pin "5") (pinfunction "SHDN_5") (pintype "input+no_connect"))
    )
  )
)
